# SparkFun_Differential_I2C_Breakout_PCA96.net
KiCad netlist of a schematic drawn in EAGLE
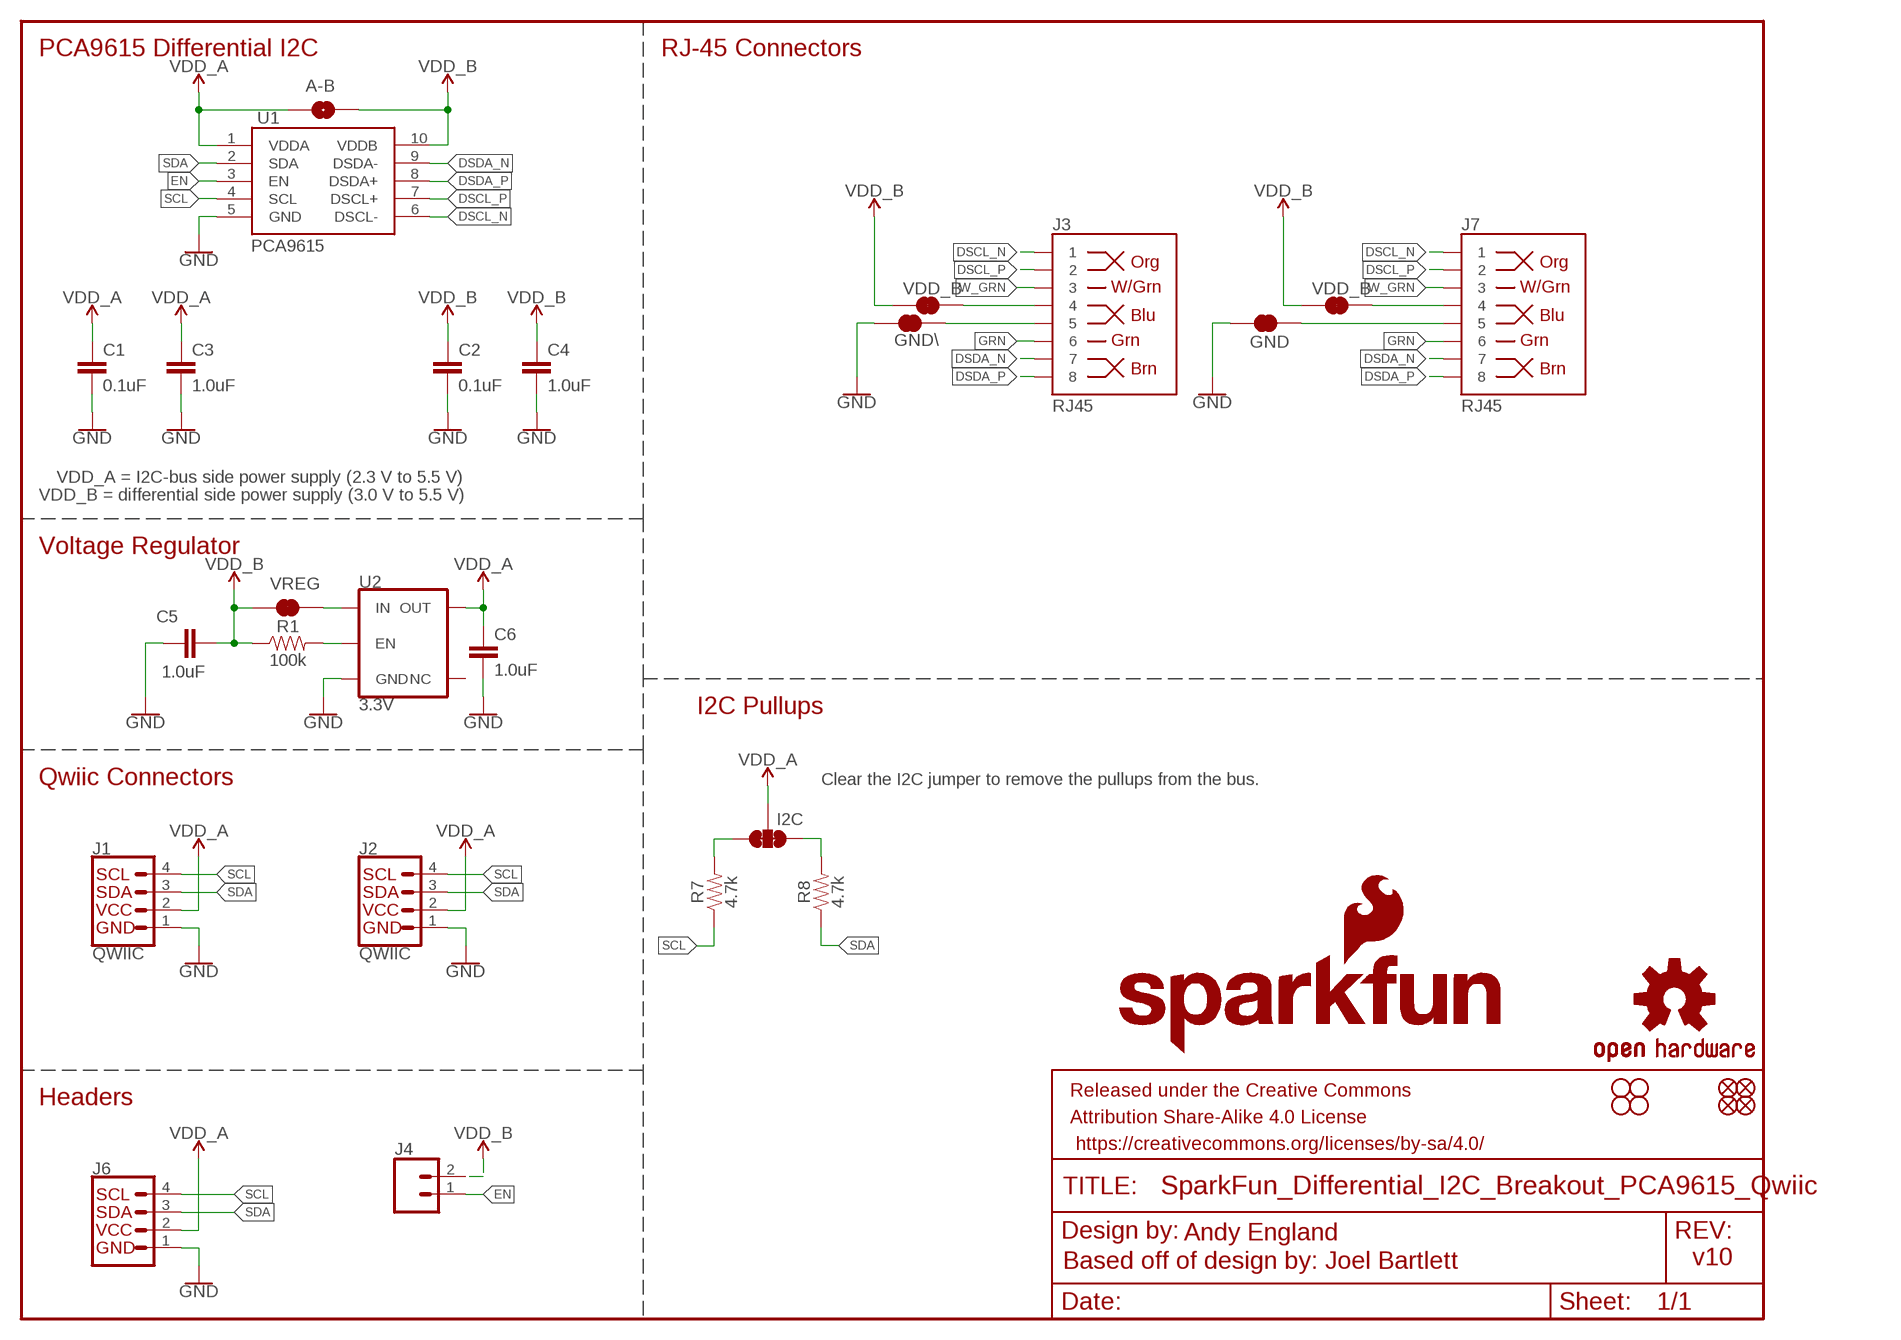
[diagram p0: schematic, sheet 1]

(export (version "E")
  (design (tool "Eeschema 10.0.6"))
  (components
    (comp (ref "A-B")
      (value "JUMPER-SMT_2_NO_SILK")
      (footprint "eagle-import:SMT-JUMPER_2_NO_SILK")
      (libsource (lib "eagle-import") (part "JUMPER-SMT_2_NO_SILK"))
    )
    (comp (ref "C1")
      (value "0.1uF")
      (footprint "eagle-import:0603")
      (libsource (lib "eagle-import") (part "0.1UF-0603-25V-(+80/-20%)"))
    )
    (comp (ref "C2")
      (value "0.1uF")
      (footprint "eagle-import:0603")
      (libsource (lib "eagle-import") (part "0.1UF-0603-25V-(+80/-20%)"))
    )
    (comp (ref "C3")
      (value "1.0uF")
      (footprint "eagle-import:0603")
      (libsource (lib "eagle-import") (part "1.0UF-0603-16V-10%"))
    )
    (comp (ref "C4")
      (value "1.0uF")
      (footprint "eagle-import:0603")
      (libsource (lib "eagle-import") (part "1.0UF-0603-16V-10%"))
    )
    (comp (ref "C5")
      (value "1.0uF")
      (footprint "eagle-import:0603")
      (libsource (lib "eagle-import") (part "1.0UF-0603-16V-10%"))
    )
    (comp (ref "C6")
      (value "1.0uF")
      (footprint "eagle-import:0603")
      (libsource (lib "eagle-import") (part "1.0UF-0603-16V-10%"))
    )
    (comp (ref "FD1")
      (value "FIDUCIALUFIDUCIAL")
      (footprint "eagle-import:FIDUCIAL-MICRO")
      (libsource (lib "eagle-import") (part "FIDUCIALUFIDUCIAL"))
    )
    (comp (ref "FD2")
      (value "FIDUCIALUFIDUCIAL")
      (footprint "eagle-import:FIDUCIAL-MICRO")
      (libsource (lib "eagle-import") (part "FIDUCIALUFIDUCIAL"))
    )
    (comp (ref "FD3")
      (value "FIDUCIALUFIDUCIAL")
      (footprint "eagle-import:FIDUCIAL-MICRO")
      (libsource (lib "eagle-import") (part "FIDUCIALUFIDUCIAL"))
    )
    (comp (ref "FD4")
      (value "FIDUCIALUFIDUCIAL")
      (footprint "eagle-import:FIDUCIAL-MICRO")
      (libsource (lib "eagle-import") (part "FIDUCIALUFIDUCIAL"))
    )
    (comp (ref "FRAME1")
      (value "FRAME-LETTER")
      (footprint "eagle-import:CREATIVE_COMMONS")
      (libsource (lib "eagle-import") (part "FRAME-LETTER"))
    )
    (comp (ref "GND\\")
      (value "JUMPER-SMT_2_NC_TRACE_SILK")
      (footprint "eagle-import:SMT-JUMPER_2_NC_TRACE_SILK")
      (libsource (lib "eagle-import") (part "JUMPER-SMT_2_NC_TRACE_SILK"))
    )
    (comp (ref "H1")
      (value "STAND-OFF")
      (footprint "eagle-import:STAND-OFF")
      (libsource (lib "eagle-import") (part "STAND-OFF"))
    )
    (comp (ref "H2")
      (value "STAND-OFF")
      (footprint "eagle-import:STAND-OFF")
      (libsource (lib "eagle-import") (part "STAND-OFF"))
    )
    (comp (ref "H3")
      (value "STAND-OFF")
      (footprint "eagle-import:STAND-OFF")
      (libsource (lib "eagle-import") (part "STAND-OFF"))
    )
    (comp (ref "H4")
      (value "STAND-OFF")
      (footprint "eagle-import:STAND-OFF")
      (libsource (lib "eagle-import") (part "STAND-OFF"))
    )
    (comp (ref "I2C")
      (value "JUMPER-SMT_3_2-NC_TRACE_SILK")
      (footprint "eagle-import:SMT-JUMPER_3_2-NC_TRACE_SILK")
      (libsource (lib "eagle-import") (part "JUMPER-SMT_3_2-NC_TRACE_SILK"))
    )
    (comp (ref "J1")
      (value "QWIIC")
      (footprint "eagle-import:JST04_1MM_RA")
      (libsource (lib "eagle-import") (part "QWIIC_CONNECTORJS-1MM"))
    )
    (comp (ref "J2")
      (value "QWIIC")
      (footprint "eagle-import:JST04_1MM_RA")
      (libsource (lib "eagle-import") (part "QWIIC_CONNECTORJS-1MM"))
    )
    (comp (ref "J3")
      (value "RJ45")
      (footprint "eagle-import:RJ45-8")
      (libsource (lib "eagle-import") (part "RJ45-8"))
    )
    (comp (ref "J4")
      (value "CONN_021X02_NO_SILK")
      (footprint "eagle-import:1X02_NO_SILK")
      (libsource (lib "eagle-import") (part "CONN_021X02_NO_SILK"))
    )
    (comp (ref "J6")
      (value "I2C_STANDARD_NO_SILK")
      (footprint "eagle-import:1X04_NO_SILK")
      (libsource (lib "eagle-import") (part "I2C_STANDARD_NO_SILK"))
    )
    (comp (ref "J7")
      (value "RJ45")
      (footprint "eagle-import:RJ45-8")
      (libsource (lib "eagle-import") (part "RJ45-8"))
    )
    (comp (ref "JP5")
      (value "JUMPER-SMT_2_NC_TRACE_SILK")
      (footprint "eagle-import:SMT-JUMPER_2_NC_TRACE_SILK")
      (libsource (lib "eagle-import") (part "JUMPER-SMT_2_NC_TRACE_SILK"))
    )
    (comp (ref "JP6")
      (value "JUMPER-SMT_2_NC_TRACE_SILK")
      (footprint "eagle-import:SMT-JUMPER_2_NC_TRACE_SILK")
      (libsource (lib "eagle-import") (part "JUMPER-SMT_2_NC_TRACE_SILK"))
    )
    (comp (ref "LOGO1")
      (value "OSHW-LOGOM")
      (footprint "eagle-import:OSHW-LOGO-M")
      (libsource (lib "eagle-import") (part "OSHW-LOGOM"))
    )
    (comp (ref "LOGO5")
      (value "SFE_LOGO_NAME_FLAME.1_INCH")
      (footprint "eagle-import:SFE_LOGO_NAME_FLAME_.1")
      (libsource (lib "eagle-import") (part "SFE_LOGO_NAME_FLAME.1_INCH"))
    )
    (comp (ref "R1")
      (value "100k")
      (footprint "eagle-import:0603")
      (libsource (lib "eagle-import") (part "100KOHM-0603-1/10W-1%"))
    )
    (comp (ref "R7")
      (value "4.7k")
      (footprint "eagle-import:0603")
      (libsource (lib "eagle-import") (part "4.7KOHM-0603-1/10W-1%"))
    )
    (comp (ref "R8")
      (value "4.7k")
      (footprint "eagle-import:0603")
      (libsource (lib "eagle-import") (part "4.7KOHM-0603-1/10W-1%"))
    )
    (comp (ref "U1")
      (value "PCA9615")
      (footprint "eagle-import:TSSOP10")
      (libsource (lib "eagle-import") (part "PCA9615"))
    )
    (comp (ref "U2")
      (value "3.3V")
      (footprint "eagle-import:SOT23-5")
      (libsource (lib "eagle-import") (part "V_REG_AP2112K-3.3V"))
    )
    (comp (ref "VDD_B")
      (value "JUMPER-SMT_2_NC_TRACE_SILK")
      (footprint "eagle-import:SMT-JUMPER_2_NC_TRACE_SILK")
      (libsource (lib "eagle-import") (part "JUMPER-SMT_2_NC_TRACE_SILK"))
    )
    (comp (ref "VREG")
      (value "JUMPER-SMT_2_NC_TRACE_SILK")
      (footprint "eagle-import:SMT-JUMPER_2_NC_TRACE_SILK")
      (libsource (lib "eagle-import") (part "JUMPER-SMT_2_NC_TRACE_SILK"))
    )
  )
  (nets
    (net (code "1") (name "DSCL_N") (class "Default")
      (node (ref "J3") (pin "1") (pinfunction "1_1") (pintype "bidirectional"))
      (node (ref "J7") (pin "1") (pinfunction "1_1") (pintype "bidirectional"))
      (node (ref "U1") (pin "6") (pinfunction "DSCL-_6") (pintype "bidirectional"))
    )
    (net (code "2") (name "DSCL_P") (class "Default")
      (node (ref "J3") (pin "2") (pinfunction "2_2") (pintype "bidirectional"))
      (node (ref "J7") (pin "2") (pinfunction "2_2") (pintype "bidirectional"))
      (node (ref "U1") (pin "7") (pinfunction "DSCL+_7") (pintype "bidirectional"))
    )
    (net (code "3") (name "DSDA_N") (class "Default")
      (node (ref "J3") (pin "7") (pinfunction "7_7") (pintype "bidirectional"))
      (node (ref "J7") (pin "7") (pinfunction "7_7") (pintype "bidirectional"))
      (node (ref "U1") (pin "9") (pinfunction "DSDA-_9") (pintype "bidirectional"))
    )
    (net (code "4") (name "DSDA_P") (class "Default")
      (node (ref "J3") (pin "8") (pinfunction "8_8") (pintype "bidirectional"))
      (node (ref "J7") (pin "8") (pinfunction "8_8") (pintype "bidirectional"))
      (node (ref "U1") (pin "8") (pinfunction "DSDA+_8") (pintype "bidirectional"))
    )
    (net (code "5") (name "EN") (class "Default")
      (node (ref "J4") (pin "1") (pinfunction "1_1") (pintype "passive"))
      (node (ref "U1") (pin "3") (pinfunction "EN_3") (pintype "bidirectional"))
    )
    (net (code "6") (name "GND") (class "Default")
      (node (ref "C1") (pin "2") (pinfunction "2_2") (pintype "passive"))
      (node (ref "C2") (pin "2") (pinfunction "2_2") (pintype "passive"))
      (node (ref "C3") (pin "2") (pinfunction "2_2") (pintype "passive"))
      (node (ref "C4") (pin "2") (pinfunction "2_2") (pintype "passive"))
      (node (ref "C5") (pin "1") (pinfunction "1_1") (pintype "passive"))
      (node (ref "C6") (pin "2") (pinfunction "2_2") (pintype "passive"))
      (node (ref "GND\\") (pin "1") (pinfunction "1_1") (pintype "passive"))
      (node (ref "J1") (pin "1") (pinfunction "1_1") (pintype "power_in"))
      (node (ref "J2") (pin "1") (pinfunction "1_1") (pintype "power_in"))
      (node (ref "J6") (pin "1") (pinfunction "GND_1") (pintype "power_in"))
      (node (ref "JP6") (pin "1") (pinfunction "1_1") (pintype "passive"))
      (node (ref "U1") (pin "5") (pinfunction "GND_5") (pintype "bidirectional"))
      (node (ref "U2") (pin "2") (pinfunction "GND_2") (pintype "input"))
    )
    (net (code "7") (name "GRN") (class "Default")
      (node (ref "J3") (pin "6") (pinfunction "6_6") (pintype "bidirectional"))
      (node (ref "J7") (pin "6") (pinfunction "6_6") (pintype "bidirectional"))
    )
    (net (code "8") (name "Net-(GND\\-Pad2)") (class "Default")
      (node (ref "GND\\") (pin "2") (pinfunction "2_2") (pintype "passive"))
      (node (ref "J3") (pin "5") (pinfunction "5_5") (pintype "bidirectional"))
    )
    (net (code "9") (name "Net-(I2C-Pad1)") (class "Default")
      (node (ref "I2C") (pin "1") (pinfunction "1_1") (pintype "passive"))
      (node (ref "R8") (pin "2") (pinfunction "2_2") (pintype "passive"))
    )
    (net (code "10") (name "Net-(I2C-Pad3)") (class "Default")
      (node (ref "I2C") (pin "3") (pinfunction "3_3") (pintype "passive"))
      (node (ref "R7") (pin "2") (pinfunction "2_2") (pintype "passive"))
    )
    (net (code "11") (name "Net-(J3-Pad4)") (class "Default")
      (node (ref "J3") (pin "4") (pinfunction "4_4") (pintype "bidirectional"))
      (node (ref "VDD_B") (pin "2") (pinfunction "2_2") (pintype "passive"))
    )
    (net (code "12") (name "Net-(J7-Pad4)") (class "Default")
      (node (ref "J7") (pin "4") (pinfunction "4_4") (pintype "bidirectional"))
      (node (ref "JP5") (pin "2") (pinfunction "2_2") (pintype "passive"))
    )
    (net (code "13") (name "Net-(J7-Pad5)") (class "Default")
      (node (ref "J7") (pin "5") (pinfunction "5_5") (pintype "bidirectional"))
      (node (ref "JP6") (pin "2") (pinfunction "2_2") (pintype "passive"))
    )
    (net (code "14") (name "Net-(U2-EN)") (class "Default")
      (node (ref "R1") (pin "2") (pinfunction "2_2") (pintype "passive"))
      (node (ref "U2") (pin "3") (pinfunction "EN_3") (pintype "input"))
    )
    (net (code "15") (name "Net-(U2-IN)") (class "Default")
      (node (ref "U2") (pin "1") (pinfunction "IN_1") (pintype "input"))
      (node (ref "VREG") (pin "2") (pinfunction "2_2") (pintype "passive"))
    )
    (net (code "16") (name "SCL") (class "Default")
      (node (ref "J1") (pin "4") (pinfunction "4_4") (pintype "passive"))
      (node (ref "J2") (pin "4") (pinfunction "4_4") (pintype "passive"))
      (node (ref "J6") (pin "4") (pinfunction "SCL_4") (pintype "passive"))
      (node (ref "R7") (pin "1") (pinfunction "1_1") (pintype "passive"))
      (node (ref "U1") (pin "4") (pinfunction "SCL_4") (pintype "bidirectional"))
    )
    (net (code "17") (name "SDA") (class "Default")
      (node (ref "J1") (pin "3") (pinfunction "3_3") (pintype "passive"))
      (node (ref "J2") (pin "3") (pinfunction "3_3") (pintype "passive"))
      (node (ref "J6") (pin "3") (pinfunction "SDA_3") (pintype "passive"))
      (node (ref "R8") (pin "1") (pinfunction "1_1") (pintype "passive"))
      (node (ref "U1") (pin "2") (pinfunction "SDA_2") (pintype "bidirectional"))
    )
    (net (code "18") (name "VDD_A") (class "Default")
      (node (ref "A-B") (pin "1") (pinfunction "1_1") (pintype "passive"))
      (node (ref "C1") (pin "1") (pinfunction "1_1") (pintype "passive"))
      (node (ref "C3") (pin "1") (pinfunction "1_1") (pintype "passive"))
      (node (ref "C6") (pin "1") (pinfunction "1_1") (pintype "passive"))
      (node (ref "I2C") (pin "2") (pinfunction "2_2") (pintype "passive"))
      (node (ref "J1") (pin "2") (pinfunction "2_2") (pintype "power_in"))
      (node (ref "J2") (pin "2") (pinfunction "2_2") (pintype "power_in"))
      (node (ref "J6") (pin "2") (pinfunction "VCC_2") (pintype "power_in"))
      (node (ref "U1") (pin "1") (pinfunction "VDDA_1") (pintype "bidirectional"))
      (node (ref "U2") (pin "5") (pinfunction "OUT_5") (pintype "passive"))
    )
    (net (code "19") (name "VDD_B") (class "Default")
      (node (ref "A-B") (pin "2") (pinfunction "2_2") (pintype "passive"))
      (node (ref "C2") (pin "1") (pinfunction "1_1") (pintype "passive"))
      (node (ref "C4") (pin "1") (pinfunction "1_1") (pintype "passive"))
      (node (ref "C5") (pin "2") (pinfunction "2_2") (pintype "passive"))
      (node (ref "J4") (pin "2") (pinfunction "2_2") (pintype "passive"))
      (node (ref "JP5") (pin "1") (pinfunction "1_1") (pintype "passive"))
      (node (ref "R1") (pin "1") (pinfunction "1_1") (pintype "passive"))
      (node (ref "U1") (pin "10") (pinfunction "VDDB_10") (pintype "bidirectional"))
      (node (ref "VDD_B") (pin "1") (pinfunction "1_1") (pintype "passive"))
      (node (ref "VREG") (pin "1") (pinfunction "1_1") (pintype "passive"))
    )
    (net (code "20") (name "W_GRN") (class "Default")
      (node (ref "J3") (pin "3") (pinfunction "3_3") (pintype "bidirectional"))
      (node (ref "J7") (pin "3") (pinfunction "3_3") (pintype "bidirectional"))
    )
    (net (code "21") (name "unconnected-(U2-NC-Pad4)") (class "Default")
      (node (ref "U2") (pin "4") (pinfunction "NC_4") (pintype "no_connect"))
    )
  )
)
